# Board.net
KiCad netlist of a schematic drawn in EAGLE
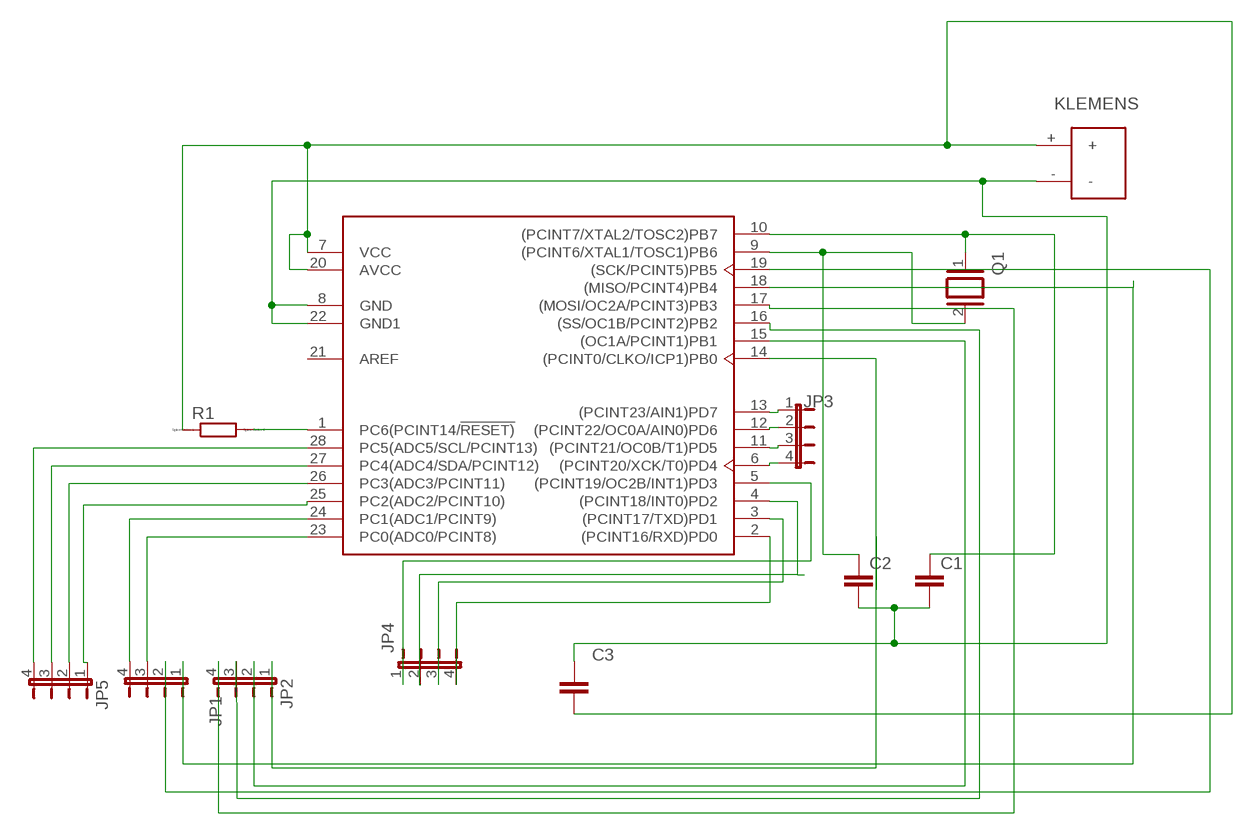
[diagram p0: schematic, sheet 1]

(export (version "E")
  (design (tool "Eeschema 10.0.6"))
  (components
    (comp (ref "C1")
      (value "C-EU050-025X075")
      (footprint "eagle-import:C050-025X075")
      (libsource (lib "eagle-import") (part "C-EU050-025X075"))
    )
    (comp (ref "C2")
      (value "C-EU050-025X075")
      (footprint "eagle-import:C050-025X075")
      (libsource (lib "eagle-import") (part "C-EU050-025X075"))
    )
    (comp (ref "C3")
      (value "C_RADIAL-12.5MM-DIA")
      (footprint "eagle-import:CAPRD550W60D1025H1250B")
      (libsource (lib "eagle-import") (part "CRADIAL-12.5MM-DIA_"))
    )
    (comp (ref "JP1")
      (value "JP4E")
      (footprint "eagle-import:JP4")
      (libsource (lib "eagle-import") (part "JP4E"))
    )
    (comp (ref "JP2")
      (value "JP4E")
      (footprint "eagle-import:JP4")
      (libsource (lib "eagle-import") (part "JP4E"))
    )
    (comp (ref "JP3")
      (value "JP4E")
      (footprint "eagle-import:JP4")
      (libsource (lib "eagle-import") (part "JP4E"))
    )
    (comp (ref "JP4")
      (value "JP4E")
      (footprint "eagle-import:JP4")
      (libsource (lib "eagle-import") (part "JP4E"))
    )
    (comp (ref "JP5")
      (value "JP4E")
      (footprint "eagle-import:JP4")
      (libsource (lib "eagle-import") (part "JP4E"))
    )
    (comp (ref "Q1")
      (value "XTAL/S")
      (footprint "eagle-import:QS")
      (libsource (lib "eagle-import") (part "XTAL/S"))
    )
    (comp (ref "R1")
      (value "R0207/10")
      (footprint "eagle-import:0207_10")
      (libsource (lib "eagle-import") (part "R0207/10"))
    )
    (comp (ref "U$1")
      (value "2X1KLEMENS")
      (footprint "eagle-import:2X1KLEMENS")
      (libsource (lib "eagle-import") (part "2X1KLEMENS"))
    )
    (comp (ref "U1")
      (value "ATMEGA328P-PU")
      (footprint "eagle-import:DIP-28")
      (fields
        (field (name "DIGIKEY_PART_NUMBER") "ATMEGA328P-PU-ND")
        (field (name "MANUFACTURER") "Microchip Technology")
        (field (name "CREATED_BY") "PCBLayout.com")
      )
      (libsource (lib "eagle-import") (part "ATMEGA328P-PU"))
    )
  )
  (nets
    (net (code "1") (name "Net-(U1-(MISO{slash}PCINT4)PB4)") (class "Default")
      (node (ref "JP1") (pin "1") (pinfunction "1_1") (pintype "passive"))
      (node (ref "U1") (pin "18") (pinfunction "(MISO/PCINT4)PB4_18") (pintype "bidirectional"))
    )
    (net (code "2") (name "Net-(U1-(MOSI{slash}OC2A{slash}PCINT3)PB3)") (class "Default")
      (node (ref "JP2") (pin "4") (pinfunction "4_4") (pintype "passive"))
      (node (ref "U1") (pin "17") (pinfunction "(MOSI/OC2A/PCINT3)PB3_17") (pintype "bidirectional"))
    )
    (net (code "3") (name "Net-(U1-(OC1A{slash}PCINT1)PB1)") (class "Default")
      (node (ref "JP2") (pin "2") (pinfunction "2_2") (pintype "passive"))
      (node (ref "U1") (pin "15") (pinfunction "(OC1A/PCINT1)PB1_15") (pintype "bidirectional"))
    )
    (net (code "4") (name "Net-(U1-(PCINT0{slash}CLKO{slash}ICP1)PB0)") (class "Default")
      (node (ref "JP2") (pin "1") (pinfunction "1_1") (pintype "passive"))
      (node (ref "U1") (pin "14") (pinfunction "(PCINT0/CLKO/ICP1)PB0_14") (pintype "bidirectional"))
    )
    (net (code "5") (name "Net-(U1-(PCINT6{slash}XTAL1{slash}TOSC1)PB6)") (class "Default")
      (node (ref "C2") (pin "1") (pinfunction "1_1") (pintype "passive"))
      (node (ref "Q1") (pin "2") (pinfunction "2_2") (pintype "passive"))
      (node (ref "U1") (pin "9") (pinfunction "(PCINT6/XTAL1/TOSC1)PB6_9") (pintype "bidirectional"))
    )
    (net (code "6") (name "Net-(U1-(PCINT7{slash}XTAL2{slash}TOSC2)PB7)") (class "Default")
      (node (ref "C1") (pin "1") (pinfunction "1_1") (pintype "passive"))
      (node (ref "Q1") (pin "1") (pinfunction "1_1") (pintype "passive"))
      (node (ref "U1") (pin "10") (pinfunction "(PCINT7/XTAL2/TOSC2)PB7_10") (pintype "bidirectional"))
    )
    (net (code "7") (name "Net-(U1-(PCINT16{slash}RXD)PD0)") (class "Default")
      (node (ref "JP4") (pin "4") (pinfunction "4_4") (pintype "passive"))
      (node (ref "U1") (pin "2") (pinfunction "(PCINT16/RXD)PD0_2") (pintype "bidirectional"))
    )
    (net (code "8") (name "Net-(U1-(PCINT17{slash}TXD)PD1)") (class "Default")
      (node (ref "JP4") (pin "3") (pinfunction "3_3") (pintype "passive"))
      (node (ref "U1") (pin "3") (pinfunction "(PCINT17/TXD)PD1_3") (pintype "bidirectional"))
    )
    (net (code "9") (name "Net-(U1-(PCINT18{slash}INT0)PD2)") (class "Default")
      (node (ref "JP4") (pin "2") (pinfunction "2_2") (pintype "passive"))
      (node (ref "U1") (pin "4") (pinfunction "(PCINT18/INT0)PD2_4") (pintype "bidirectional"))
    )
    (net (code "10") (name "Net-(U1-(PCINT19{slash}OC2B{slash}INT1)PD3)") (class "Default")
      (node (ref "JP4") (pin "1") (pinfunction "1_1") (pintype "passive"))
      (node (ref "U1") (pin "5") (pinfunction "(PCINT19/OC2B/INT1)PD3_5") (pintype "bidirectional"))
    )
    (net (code "11") (name "Net-(U1-(PCINT20{slash}XCK{slash}T0)PD4)") (class "Default")
      (node (ref "JP3") (pin "4") (pinfunction "4_4") (pintype "passive"))
      (node (ref "U1") (pin "6") (pinfunction "(PCINT20/XCK/T0)PD4_6") (pintype "bidirectional"))
    )
    (net (code "12") (name "Net-(U1-(PCINT21{slash}OC0B{slash}T1)PD5)") (class "Default")
      (node (ref "JP3") (pin "3") (pinfunction "3_3") (pintype "passive"))
      (node (ref "U1") (pin "11") (pinfunction "(PCINT21/OC0B/T1)PD5_11") (pintype "bidirectional"))
    )
    (net (code "13") (name "Net-(U1-(PCINT22{slash}OC0A{slash}AIN0)PD6)") (class "Default")
      (node (ref "JP3") (pin "2") (pinfunction "2_2") (pintype "passive"))
      (node (ref "U1") (pin "12") (pinfunction "(PCINT22/OC0A/AIN0)PD6_12") (pintype "bidirectional"))
    )
    (net (code "14") (name "Net-(U1-(PCINT23{slash}AIN1)PD7)") (class "Default")
      (node (ref "JP3") (pin "1") (pinfunction "1_1") (pintype "passive"))
      (node (ref "U1") (pin "13") (pinfunction "(PCINT23/AIN1)PD7_13") (pintype "bidirectional"))
    )
    (net (code "15") (name "Net-(U1-(SCK{slash}PCINT5)PB5)") (class "Default")
      (node (ref "JP1") (pin "2") (pinfunction "2_2") (pintype "passive"))
      (node (ref "U1") (pin "19") (pinfunction "(SCK/PCINT5)PB5_19") (pintype "bidirectional"))
    )
    (net (code "16") (name "Net-(U1-(SS{slash}OC1B{slash}PCINT2)PB2)") (class "Default")
      (node (ref "JP2") (pin "3") (pinfunction "3_3") (pintype "passive"))
      (node (ref "U1") (pin "16") (pinfunction "(SS/OC1B/PCINT2)PB2_16") (pintype "bidirectional"))
    )
    (net (code "17") (name "Net-(U1-AVCC)") (class "Default")
      (node (ref "C3") (pin "2") (pinfunction "2_2") (pintype "passive"))
      (node (ref "R1") (pin "1") (pinfunction "1_1") (pintype "passive"))
      (node (ref "U$1") (pin "+") (pinfunction "+_+") (pintype "bidirectional"))
      (node (ref "U1") (pin "20") (pinfunction "AVCC_20") (pintype "power_in"))
      (node (ref "U1") (pin "7") (pinfunction "VCC_7") (pintype "power_in"))
    )
    (net (code "18") (name "Net-(U1-GND)") (class "Default")
      (node (ref "C1") (pin "2") (pinfunction "2_2") (pintype "passive"))
      (node (ref "C2") (pin "2") (pinfunction "2_2") (pintype "passive"))
      (node (ref "C3") (pin "1") (pinfunction "1_1") (pintype "passive"))
      (node (ref "U$1") (pin "-") (pinfunction "-_-") (pintype "bidirectional"))
      (node (ref "U1") (pin "22") (pinfunction "GND1_22") (pintype "power_in"))
      (node (ref "U1") (pin "8") (pinfunction "GND_8") (pintype "power_in"))
    )
    (net (code "19") (name "Net-(U1-PC0(ADC0{slash}PCINT8))") (class "Default")
      (node (ref "JP1") (pin "3") (pinfunction "3_3") (pintype "passive"))
      (node (ref "U1") (pin "23") (pinfunction "PC0(ADC0/PCINT8)_23") (pintype "bidirectional"))
    )
    (net (code "20") (name "Net-(U1-PC1(ADC1{slash}PCINT9))") (class "Default")
      (node (ref "JP1") (pin "4") (pinfunction "4_4") (pintype "passive"))
      (node (ref "U1") (pin "24") (pinfunction "PC1(ADC1/PCINT9)_24") (pintype "bidirectional"))
    )
    (net (code "21") (name "Net-(U1-PC2(ADC2{slash}PCINT10))") (class "Default")
      (node (ref "JP5") (pin "1") (pinfunction "1_1") (pintype "passive"))
      (node (ref "U1") (pin "25") (pinfunction "PC2(ADC2/PCINT10)_25") (pintype "bidirectional"))
    )
    (net (code "22") (name "Net-(U1-PC3(ADC3{slash}PCINT11))") (class "Default")
      (node (ref "JP5") (pin "2") (pinfunction "2_2") (pintype "passive"))
      (node (ref "U1") (pin "26") (pinfunction "PC3(ADC3/PCINT11)_26") (pintype "bidirectional"))
    )
    (net (code "23") (name "Net-(U1-PC4(ADC4{slash}SDA{slash}PCINT12))") (class "Default")
      (node (ref "JP5") (pin "3") (pinfunction "3_3") (pintype "passive"))
      (node (ref "U1") (pin "27") (pinfunction "PC4(ADC4/SDA/PCINT12)_27") (pintype "bidirectional"))
    )
    (net (code "24") (name "Net-(U1-PC5(ADC5{slash}SCL{slash}PCINT13))") (class "Default")
      (node (ref "JP5") (pin "4") (pinfunction "4_4") (pintype "passive"))
      (node (ref "U1") (pin "28") (pinfunction "PC5(ADC5/SCL/PCINT13)_28") (pintype "bidirectional"))
    )
    (net (code "25") (name "Net-(U1-PC6(PCINT14{slash}~{RESET}))") (class "Default")
      (node (ref "R1") (pin "2") (pinfunction "2_2") (pintype "passive"))
      (node (ref "U1") (pin "1") (pinfunction "PC6(PCINT14/~{RESET})_1") (pintype "bidirectional"))
    )
    (net (code "26") (name "unconnected-(U1-AREF-Pad21)") (class "Default")
      (node (ref "U1") (pin "21") (pinfunction "AREF_21") (pintype "input"))
    )
  )
)
